# MC-10_Mod_A_V_revA.net
KiCad netlist of a schematic drawn in EAGLE
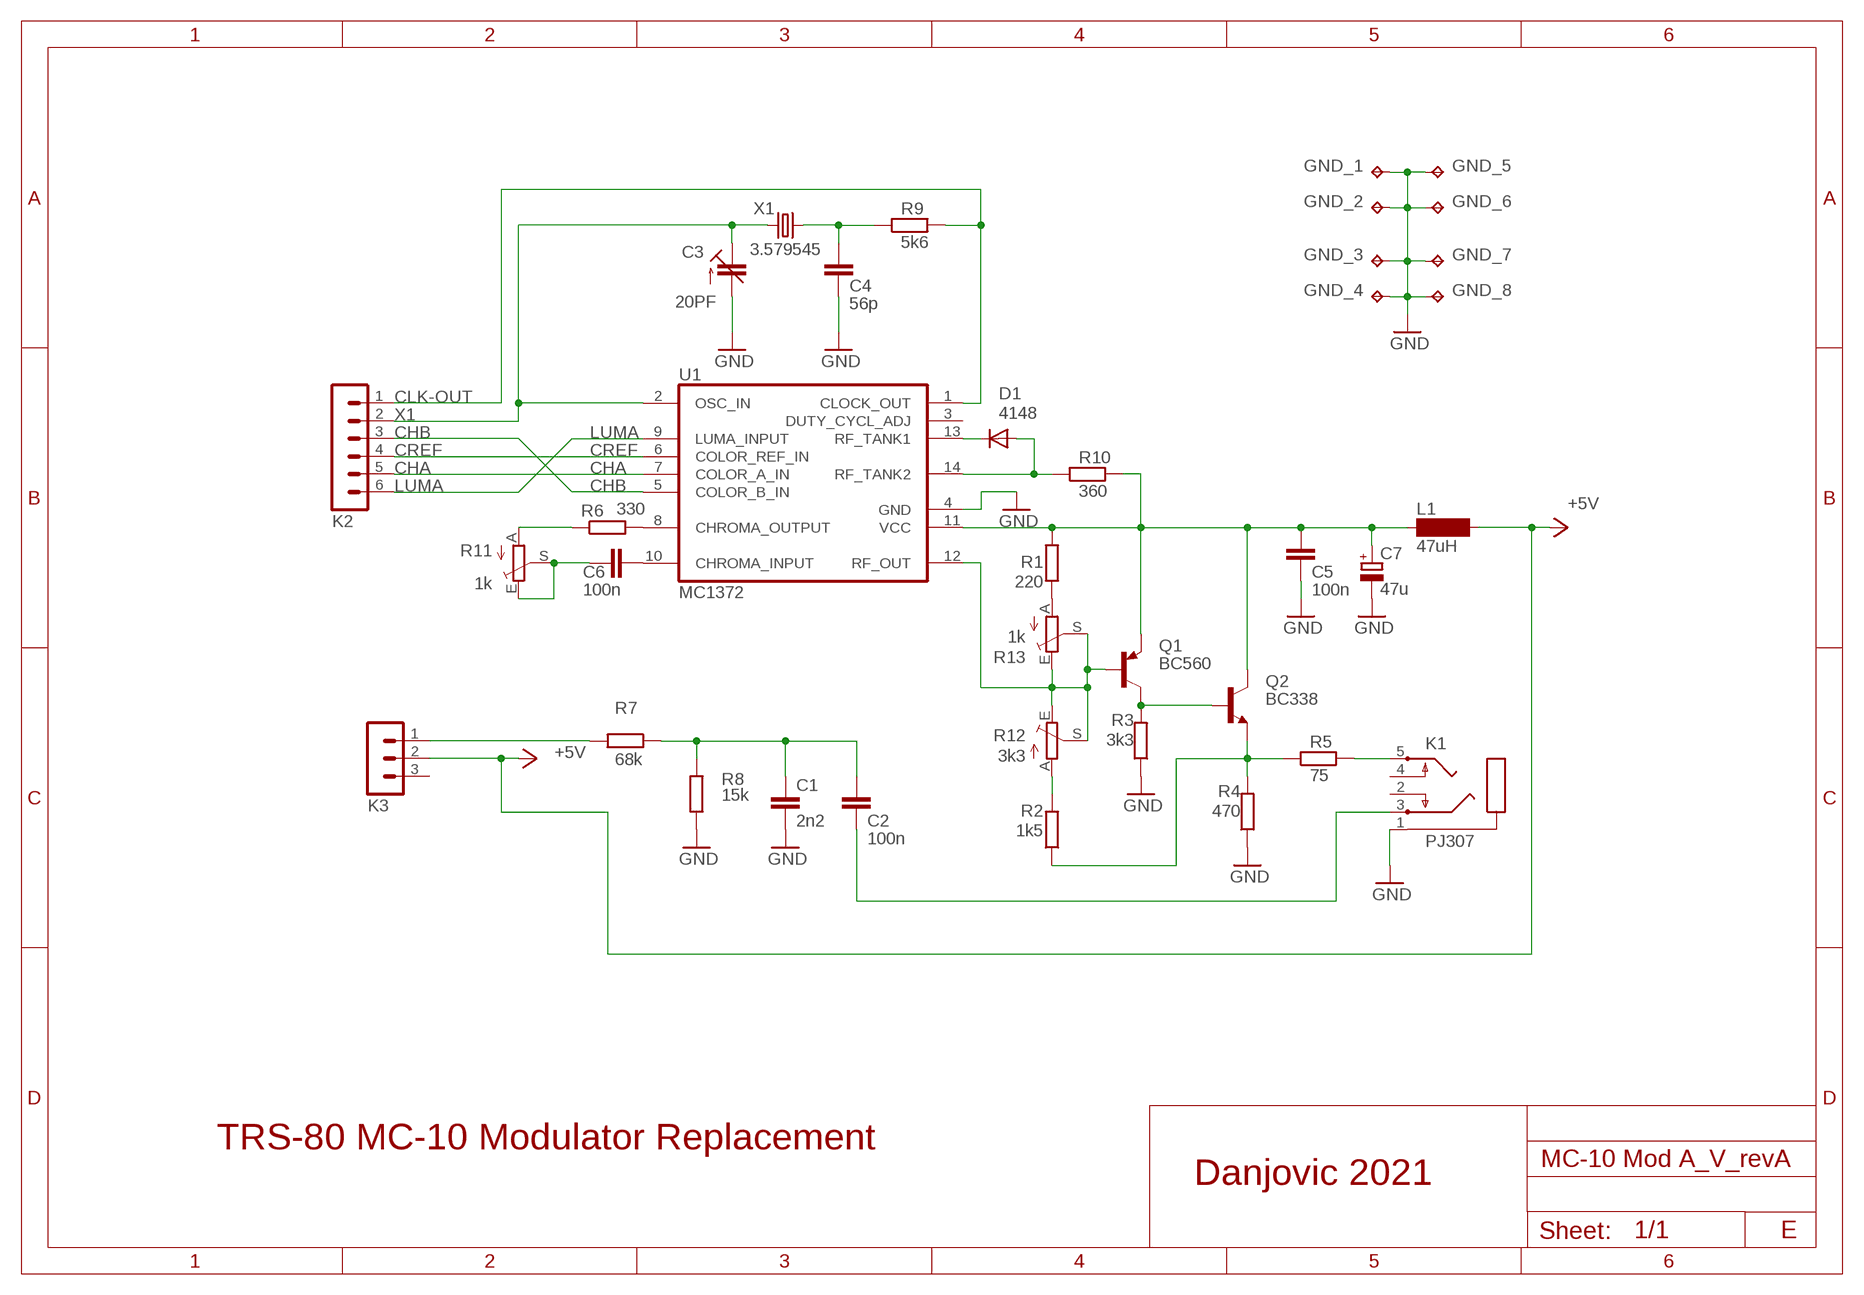
[diagram p0: schematic, sheet 1]

(export (version "E")
  (design (tool "Eeschema 10.0.6"))
  (components
    (comp (ref "C1")
      (value "2n2")
      (footprint "eagle-import:C050-024X044")
      (libsource (lib "eagle-import") (part "C-EU050-024X044"))
    )
    (comp (ref "C2")
      (value "100n")
      (footprint "eagle-import:C050-024X044")
      (libsource (lib "eagle-import") (part "C-EU050-024X044"))
    )
    (comp (ref "C3")
      (value "20PF")
      (footprint "eagle-import:CTRIM3050.504")
      (libsource (lib "eagle-import") (part "C-TRIMM3050.504"))
    )
    (comp (ref "C4")
      (value "56p")
      (footprint "eagle-import:C025-024X044")
      (libsource (lib "eagle-import") (part "C-EU025-024X044"))
    )
    (comp (ref "C5")
      (value "100n")
      (footprint "eagle-import:C050-024X044")
      (libsource (lib "eagle-import") (part "C-EU050-024X044"))
    )
    (comp (ref "C6")
      (value "100n")
      (footprint "eagle-import:C050-024X044")
      (libsource (lib "eagle-import") (part "C-EU050-024X044"))
    )
    (comp (ref "C7")
      (value "47u")
      (footprint "eagle-import:E2,5-5")
      (libsource (lib "eagle-import") (part "CPOL-EUE2.5-5"))
    )
    (comp (ref "D1")
      (value "4148")
      (footprint "eagle-import:D-5")
      (libsource (lib "eagle-import") (part "DIODE-D-5"))
    )
    (comp (ref "GND_1")
      (value "TPPAD1-13")
      (footprint "eagle-import:P1-13")
      (libsource (lib "eagle-import") (part "TPPAD1-13"))
    )
    (comp (ref "GND_2")
      (value "TPPAD1-13")
      (footprint "eagle-import:P1-13")
      (libsource (lib "eagle-import") (part "TPPAD1-13"))
    )
    (comp (ref "GND_3")
      (value "TPPAD1-13")
      (footprint "eagle-import:P1-13")
      (libsource (lib "eagle-import") (part "TPPAD1-13"))
    )
    (comp (ref "GND_4")
      (value "TPPAD1-13")
      (footprint "eagle-import:P1-13")
      (libsource (lib "eagle-import") (part "TPPAD1-13"))
    )
    (comp (ref "GND_5")
      (value "TPPAD1-13")
      (footprint "eagle-import:P1-13")
      (libsource (lib "eagle-import") (part "TPPAD1-13"))
    )
    (comp (ref "GND_6")
      (value "TPPAD1-13")
      (footprint "eagle-import:P1-13")
      (libsource (lib "eagle-import") (part "TPPAD1-13"))
    )
    (comp (ref "GND_7")
      (value "TPPAD1-13")
      (footprint "eagle-import:P1-13")
      (libsource (lib "eagle-import") (part "TPPAD1-13"))
    )
    (comp (ref "GND_8")
      (value "TPPAD1-13")
      (footprint "eagle-import:P1-13")
      (libsource (lib "eagle-import") (part "TPPAD1-13"))
    )
    (comp (ref "K1")
      (value "PJ307")
      (footprint "eagle-import:PJ307")
      (libsource (lib "eagle-import") (part "PJ307"))
    )
    (comp (ref "K2")
      (value "MA06-1")
      (footprint "eagle-import:MA06-1")
      (libsource (lib "eagle-import") (part "MA06-1"))
    )
    (comp (ref "K3")
      (value "MA03-1")
      (footprint "eagle-import:MA03-1")
      (libsource (lib "eagle-import") (part "MA03-1"))
    )
    (comp (ref "L1")
      (value "47uH")
      (footprint "eagle-import:BS75")
      (libsource (lib "eagle-import") (part "BS75"))
    )
    (comp (ref "Q1")
      (value "BC560")
      (footprint "eagle-import:TO92-EBC")
      (libsource (lib "eagle-import") (part "BC327"))
    )
    (comp (ref "Q2")
      (value "BC338")
      (footprint "eagle-import:TO92-EBC")
      (libsource (lib "eagle-import") (part "BC338"))
    )
    (comp (ref "R1")
      (value "220")
      (footprint "eagle-import:0204_7")
      (libsource (lib "eagle-import") (part "R-EU_0204/7"))
    )
    (comp (ref "R2")
      (value "1k5")
      (footprint "eagle-import:0204_7")
      (libsource (lib "eagle-import") (part "R-EU_0204/7"))
    )
    (comp (ref "R3")
      (value "3k3")
      (footprint "eagle-import:0204_7")
      (libsource (lib "eagle-import") (part "R-EU_0204/7"))
    )
    (comp (ref "R4")
      (value "470")
      (footprint "eagle-import:0204_7")
      (libsource (lib "eagle-import") (part "R-EU_0204/7"))
    )
    (comp (ref "R5")
      (value "75")
      (footprint "eagle-import:0204_7")
      (libsource (lib "eagle-import") (part "R-EU_0204/7"))
    )
    (comp (ref "R6")
      (value "330")
      (footprint "eagle-import:0204_7")
      (libsource (lib "eagle-import") (part "R-EU_0204/7"))
    )
    (comp (ref "R7")
      (value "68k")
      (footprint "eagle-import:0204_7")
      (libsource (lib "eagle-import") (part "R-EU_0204/7"))
    )
    (comp (ref "R8")
      (value "15k")
      (footprint "eagle-import:0204_7")
      (libsource (lib "eagle-import") (part "R-EU_0204/7"))
    )
    (comp (ref "R9")
      (value "5k6")
      (footprint "eagle-import:0204_7")
      (libsource (lib "eagle-import") (part "R-EU_0204/7"))
    )
    (comp (ref "R10")
      (value "360")
      (footprint "eagle-import:0204_7")
      (libsource (lib "eagle-import") (part "R-EU_0204/7"))
    )
    (comp (ref "R11")
      (value "1k")
      (footprint "eagle-import:RS3")
      (libsource (lib "eagle-import") (part "TRIM_EU-RS3"))
    )
    (comp (ref "R12")
      (value "3k3")
      (footprint "eagle-import:RS3")
      (libsource (lib "eagle-import") (part "TRIM_EU-RS3"))
    )
    (comp (ref "R13")
      (value "1k")
      (footprint "eagle-import:RS3")
      (libsource (lib "eagle-import") (part "TRIM_EU-RS3"))
    )
    (comp (ref "U1")
      (value "MC1372")
      (footprint "eagle-import:DIL14")
      (libsource (lib "eagle-import") (part "MC1372"))
    )
    (comp (ref "X1")
      (value "3.579545")
      (footprint "eagle-import:HC49U70")
      (libsource (lib "eagle-import") (part "CRYSTALHC49U70"))
    )
  )
  (nets
    (net (code "1") (name "+5V") (class "Default")
      (node (ref "K3") (pin "2") (pinfunction "2_2") (pintype "passive"))
      (node (ref "L1") (pin "2") (pinfunction "2_2") (pintype "passive"))
    )
    (net (code "2") (name "/CHA") (class "Default")
      (node (ref "K2") (pin "5") (pinfunction "5_5") (pintype "passive"))
      (node (ref "U1") (pin "7") (pinfunction "COLOR_A_IN_7") (pintype "input"))
    )
    (net (code "3") (name "/CHB") (class "Default")
      (node (ref "K2") (pin "3") (pinfunction "3_3") (pintype "passive"))
      (node (ref "U1") (pin "5") (pinfunction "COLOR_B_IN_5") (pintype "input"))
    )
    (net (code "4") (name "/CLK-OUT") (class "Default")
      (node (ref "K2") (pin "1") (pinfunction "1_1") (pintype "passive"))
      (node (ref "R9") (pin "2") (pinfunction "2_2") (pintype "passive"))
      (node (ref "U1") (pin "1") (pinfunction "CLOCK_OUT_1") (pintype "output"))
    )
    (net (code "5") (name "/CREF") (class "Default")
      (node (ref "K2") (pin "4") (pinfunction "4_4") (pintype "passive"))
      (node (ref "U1") (pin "6") (pinfunction "COLOR_REF_IN_6") (pintype "input"))
    )
    (net (code "6") (name "/LUMA") (class "Default")
      (node (ref "K2") (pin "6") (pinfunction "6_6") (pintype "passive"))
      (node (ref "U1") (pin "9") (pinfunction "LUMA_INPUT_9") (pintype "input"))
    )
    (net (code "7") (name "/X1") (class "Default")
      (node (ref "C3") (pin "1") (pinfunction "E_1") (pintype "passive"))
      (node (ref "K2") (pin "2") (pinfunction "2_2") (pintype "passive"))
      (node (ref "U1") (pin "2") (pinfunction "OSC_IN_2") (pintype "tri_state"))
      (node (ref "X1") (pin "1") (pinfunction "1_1") (pintype "passive"))
    )
    (net (code "8") (name "GND") (class "Default")
      (node (ref "C1") (pin "2") (pinfunction "2_2") (pintype "passive"))
      (node (ref "C3") (pin "2") (pinfunction "A_2") (pintype "passive"))
      (node (ref "C4") (pin "2") (pinfunction "2_2") (pintype "passive"))
      (node (ref "C5") (pin "2") (pinfunction "2_2") (pintype "passive"))
      (node (ref "C7") (pin "-") (pinfunction "-_-") (pintype "passive"))
      (node (ref "GND_1") (pin "TP") (pinfunction "TP_TP") (pintype "input"))
      (node (ref "GND_2") (pin "TP") (pinfunction "TP_TP") (pintype "input"))
      (node (ref "GND_3") (pin "TP") (pinfunction "TP_TP") (pintype "input"))
      (node (ref "GND_4") (pin "TP") (pinfunction "TP_TP") (pintype "input"))
      (node (ref "GND_5") (pin "TP") (pinfunction "TP_TP") (pintype "input"))
      (node (ref "GND_6") (pin "TP") (pinfunction "TP_TP") (pintype "input"))
      (node (ref "GND_7") (pin "TP") (pinfunction "TP_TP") (pintype "input"))
      (node (ref "GND_8") (pin "TP") (pinfunction "TP_TP") (pintype "input"))
      (node (ref "K1") (pin "1") (pinfunction "1_1") (pintype "passive"))
      (node (ref "R3") (pin "1") (pinfunction "1_1") (pintype "passive"))
      (node (ref "R4") (pin "1") (pinfunction "1_1") (pintype "passive"))
      (node (ref "R8") (pin "1") (pinfunction "1_1") (pintype "passive"))
      (node (ref "U1") (pin "4") (pinfunction "GND_4") (pintype "power_in"))
    )
    (net (code "9") (name "Net-(C1-Pad1)") (class "Default")
      (node (ref "C1") (pin "1") (pinfunction "1_1") (pintype "passive"))
      (node (ref "C2") (pin "1") (pinfunction "1_1") (pintype "passive"))
      (node (ref "R7") (pin "1") (pinfunction "1_1") (pintype "passive"))
      (node (ref "R8") (pin "2") (pinfunction "2_2") (pintype "passive"))
    )
    (net (code "10") (name "Net-(C2-Pad2)") (class "Default")
      (node (ref "C2") (pin "2") (pinfunction "2_2") (pintype "passive"))
      (node (ref "K1") (pin "3") (pinfunction "3_3") (pintype "passive"))
    )
    (net (code "11") (name "Net-(C4-Pad1)") (class "Default")
      (node (ref "C4") (pin "1") (pinfunction "1_1") (pintype "passive"))
      (node (ref "R9") (pin "1") (pinfunction "1_1") (pintype "passive"))
      (node (ref "X1") (pin "2") (pinfunction "2_2") (pintype "passive"))
    )
    (net (code "12") (name "Net-(C6-Pad1)") (class "Default")
      (node (ref "C6") (pin "1") (pinfunction "1_1") (pintype "passive"))
      (node (ref "R11") (pin "E") (pinfunction "E_E") (pintype "passive"))
      (node (ref "R11") (pin "S") (pinfunction "S_S") (pintype "passive"))
    )
    (net (code "13") (name "Net-(K1-Pad5)") (class "Default")
      (node (ref "K1") (pin "5") (pinfunction "5_5") (pintype "passive"))
      (node (ref "R5") (pin "2") (pinfunction "2_2") (pintype "passive"))
    )
    (net (code "14") (name "Net-(K3-Pad1)") (class "Default")
      (node (ref "K3") (pin "1") (pinfunction "1_1") (pintype "passive"))
      (node (ref "R7") (pin "2") (pinfunction "2_2") (pintype "passive"))
    )
    (net (code "15") (name "Net-(Q1-PadC)") (class "Default")
      (node (ref "Q1") (pin "C") (pinfunction "C_C") (pintype "passive"))
      (node (ref "Q2") (pin "B") (pinfunction "B_B") (pintype "passive"))
      (node (ref "R3") (pin "2") (pinfunction "2_2") (pintype "passive"))
    )
    (net (code "16") (name "Net-(Q2-PadE)") (class "Default")
      (node (ref "Q2") (pin "E") (pinfunction "E_E") (pintype "passive"))
      (node (ref "R2") (pin "1") (pinfunction "1_1") (pintype "passive"))
      (node (ref "R4") (pin "2") (pinfunction "2_2") (pintype "passive"))
      (node (ref "R5") (pin "1") (pinfunction "1_1") (pintype "passive"))
    )
    (net (code "17") (name "Net-(R1-Pad1)") (class "Default")
      (node (ref "R1") (pin "1") (pinfunction "1_1") (pintype "passive"))
      (node (ref "R13") (pin "A") (pinfunction "A_A") (pintype "passive"))
    )
    (net (code "18") (name "Net-(R11-PadA)") (class "Default")
      (node (ref "R11") (pin "A") (pinfunction "A_A") (pintype "passive"))
      (node (ref "R6") (pin "1") (pinfunction "1_1") (pintype "passive"))
    )
    (net (code "19") (name "Net-(R12-PadA)") (class "Default")
      (node (ref "R12") (pin "A") (pinfunction "A_A") (pintype "passive"))
      (node (ref "R2") (pin "2") (pinfunction "2_2") (pintype "passive"))
    )
    (net (code "20") (name "Net-(U1-CHROMA_INPUT)") (class "Default")
      (node (ref "C6") (pin "2") (pinfunction "2_2") (pintype "passive"))
      (node (ref "U1") (pin "10") (pinfunction "CHROMA_INPUT_10") (pintype "input"))
    )
    (net (code "21") (name "Net-(U1-CHROMA_OUTPUT)") (class "Default")
      (node (ref "R6") (pin "2") (pinfunction "2_2") (pintype "passive"))
      (node (ref "U1") (pin "8") (pinfunction "CHROMA_OUTPUT_8") (pintype "output"))
    )
    (net (code "22") (name "Net-(U1-RF_OUT)") (class "Default")
      (node (ref "Q1") (pin "B") (pinfunction "B_B") (pintype "passive"))
      (node (ref "R12") (pin "E") (pinfunction "E_E") (pintype "passive"))
      (node (ref "R12") (pin "S") (pinfunction "S_S") (pintype "passive"))
      (node (ref "R13") (pin "E") (pinfunction "E_E") (pintype "passive"))
      (node (ref "R13") (pin "S") (pinfunction "S_S") (pintype "passive"))
      (node (ref "U1") (pin "12") (pinfunction "RF_OUT_12") (pintype "output"))
    )
    (net (code "23") (name "Net-(U1-RF_TANK1)") (class "Default")
      (node (ref "D1") (pin "C") (pinfunction "C_C") (pintype "passive"))
      (node (ref "U1") (pin "13") (pinfunction "RF_TANK1_13") (pintype "tri_state"))
    )
    (net (code "24") (name "Net-(U1-RF_TANK2)") (class "Default")
      (node (ref "D1") (pin "A") (pinfunction "A_A") (pintype "passive"))
      (node (ref "R10") (pin "1") (pinfunction "1_1") (pintype "passive"))
      (node (ref "U1") (pin "14") (pinfunction "RF_TANK2_14") (pintype "tri_state"))
    )
    (net (code "25") (name "Net-(U1-VCC)") (class "Default")
      (node (ref "C5") (pin "1") (pinfunction "1_1") (pintype "passive"))
      (node (ref "C7") (pin "+") (pinfunction "+_+") (pintype "passive"))
      (node (ref "L1") (pin "1") (pinfunction "1_1") (pintype "passive"))
      (node (ref "Q1") (pin "E") (pinfunction "E_E") (pintype "passive"))
      (node (ref "Q2") (pin "C") (pinfunction "C_C") (pintype "passive"))
      (node (ref "R1") (pin "2") (pinfunction "2_2") (pintype "passive"))
      (node (ref "R10") (pin "2") (pinfunction "2_2") (pintype "passive"))
      (node (ref "U1") (pin "11") (pinfunction "VCC_11") (pintype "power_in"))
    )
    (net (code "26") (name "unconnected-(K1-Pad2)") (class "Default")
      (node (ref "K1") (pin "2") (pinfunction "2_2") (pintype "passive"))
    )
    (net (code "27") (name "unconnected-(K1-Pad4)") (class "Default")
      (node (ref "K1") (pin "4") (pinfunction "4_4") (pintype "passive"))
    )
    (net (code "28") (name "unconnected-(K3-Pad3)") (class "Default")
      (node (ref "K3") (pin "3") (pinfunction "3_3") (pintype "passive"))
    )
    (net (code "29") (name "unconnected-(U1-DUTY_CYCL_ADJ-Pad3)") (class "Default")
      (node (ref "U1") (pin "3") (pinfunction "DUTY_CYCL_ADJ_3") (pintype "input"))
    )
  )
)
